# Sheet1.net
KiCad netlist of a schematic drawn in Altium Designer
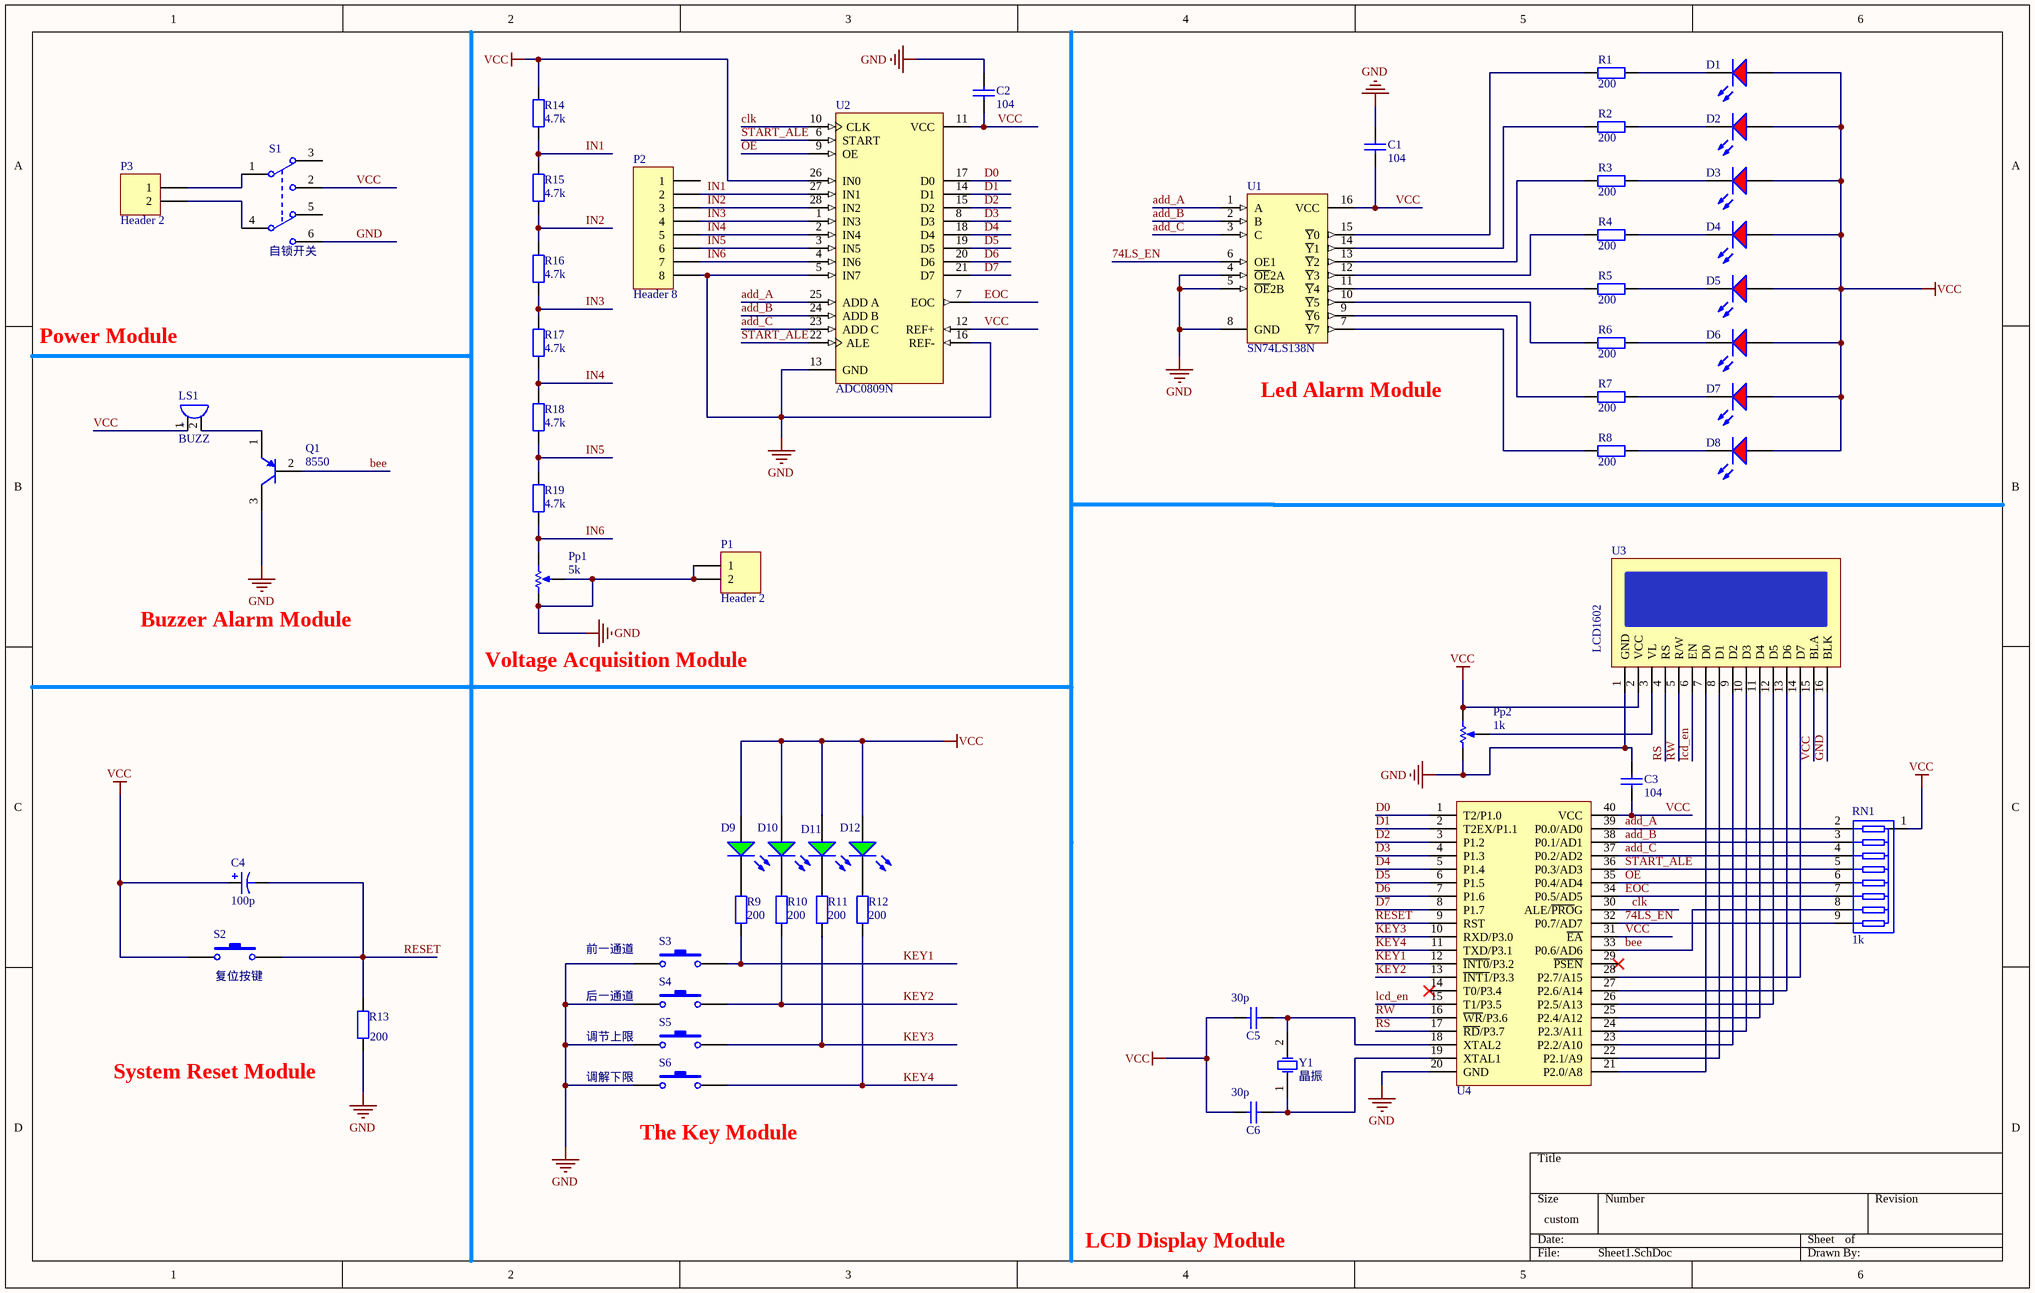
[diagram p0: Sheet1.SchDoc]

(export (version "E")
  (design (tool "Eeschema 10.0.6"))
  (components
    (comp (ref "C1")
      (value "104")
      (footprint "CAP-0.1")
      (description "Capacitor 瓷片电容 无极性电容")
      (fields (field (name "PUBLISHER") "Altium Limited"))
      (libsource (lib "02-Miscellaneous_Devices_ZSF_Library") (part "Cap_ceramic"))
    )
    (comp (ref "C2")
      (value "104")
      (footprint "CAP-0.1")
      (description "Capacitor 瓷片电容 无极性电容")
      (fields (field (name "PUBLISHER") "Altium Limited"))
      (libsource (lib "02-Miscellaneous_Devices_ZSF_Library") (part "Cap_ceramic"))
    )
    (comp (ref "C3")
      (value "104")
      (footprint "CAP-0.1")
      (description "Capacitor 瓷片电容 无极性电容")
      (fields (field (name "PUBLISHER") "Altium Limited"))
      (libsource (lib "02-Miscellaneous_Devices_ZSF_Library") (part "Cap_ceramic"))
    )
    (comp (ref "C4")
      (value "100p")
      (footprint "CAP 2.0*5*11")
      (description "Polarized Capacitor (Axial)")
      (fields (field (name "PUBLISHER") "Altium Limited"))
      (libsource (lib "02-Miscellaneous_Devices_ZSF_Library") (part "Cap Pol2"))
    )
    (comp (ref "C5")
      (value "30p")
      (footprint "CAP-0.1")
      (description "Capacitor 瓷片电容 无极性电容")
      (fields (field (name "PUBLISHER") "Altium Limited"))
      (libsource (lib "02-Miscellaneous_Devices_ZSF_Library") (part "Cap_ceramic"))
    )
    (comp (ref "C6")
      (value "30p")
      (footprint "CAP-0.1")
      (description "Capacitor 瓷片电容 无极性电容")
      (fields (field (name "PUBLISHER") "Altium Limited"))
      (libsource (lib "02-Miscellaneous_Devices_ZSF_Library") (part "Cap_ceramic"))
    )
    (comp (ref "D1")
      (value "直径5mm的红灯")
      (footprint "LED 5MM-R")
      (description "直径5mm的发光二极管")
      (libsource (lib "02-Miscellaneous_Devices_ZSF_Library") (part "LED_5#红灯"))
    )
    (comp (ref "D2")
      (value "直径5mm的红灯")
      (footprint "LED 5MM-R")
      (description "直径5mm的发光二极管")
      (libsource (lib "02-Miscellaneous_Devices_ZSF_Library") (part "LED_5#红灯"))
    )
    (comp (ref "D3")
      (value "直径5mm的红灯")
      (footprint "LED 5MM-R")
      (description "直径5mm的发光二极管")
      (libsource (lib "02-Miscellaneous_Devices_ZSF_Library") (part "LED_5#红灯"))
    )
    (comp (ref "D4")
      (value "直径5mm的红灯")
      (footprint "LED 5MM-R")
      (description "直径5mm的发光二极管")
      (libsource (lib "02-Miscellaneous_Devices_ZSF_Library") (part "LED_5#红灯"))
    )
    (comp (ref "D5")
      (value "直径5mm的红灯")
      (footprint "LED 5MM-R")
      (description "直径5mm的发光二极管")
      (libsource (lib "02-Miscellaneous_Devices_ZSF_Library") (part "LED_5#红灯"))
    )
    (comp (ref "D6")
      (value "直径5mm的红灯")
      (footprint "LED 5MM-R")
      (description "直径5mm的发光二极管")
      (libsource (lib "02-Miscellaneous_Devices_ZSF_Library") (part "LED_5#红灯"))
    )
    (comp (ref "D7")
      (value "直径5mm的红灯")
      (footprint "LED 5MM-R")
      (description "直径5mm的发光二极管")
      (libsource (lib "02-Miscellaneous_Devices_ZSF_Library") (part "LED_5#红灯"))
    )
    (comp (ref "D8")
      (value "直径5mm的红灯")
      (footprint "LED 5MM-R")
      (description "直径5mm的发光二极管")
      (libsource (lib "02-Miscellaneous_Devices_ZSF_Library") (part "LED_5#红灯"))
    )
    (comp (ref "D9")
      (value "直径5mm的绿灯")
      (footprint "LED 3MM-G")
      (description "直径5mm的发光二极管")
      (libsource (lib "02-Miscellaneous_Devices_ZSF_Library") (part "LED_5#绿灯"))
    )
    (comp (ref "D10")
      (value "直径5mm的绿灯")
      (footprint "LED 3MM-G")
      (description "直径5mm的发光二极管")
      (libsource (lib "02-Miscellaneous_Devices_ZSF_Library") (part "LED_5#绿灯"))
    )
    (comp (ref "D11")
      (value "直径5mm的绿灯")
      (footprint "LED 3MM-G")
      (description "直径5mm的发光二极管")
      (libsource (lib "02-Miscellaneous_Devices_ZSF_Library") (part "LED_5#绿灯"))
    )
    (comp (ref "D12")
      (value "直径5mm的绿灯")
      (footprint "LED 3MM-G")
      (description "直径5mm的发光二极管")
      (libsource (lib "02-Miscellaneous_Devices_ZSF_Library") (part "LED_5#绿灯"))
    )
    (comp (ref "LS1")
      (value "BUZZ")
      (footprint "Beep_small")
      (description "蜂鸣器")
      (libsource (lib "02-Miscellaneous_Devices_ZSF_Library") (part "BUZZ"))
    )
    (comp (ref "P1")
      (value "Header 2")
      (footprint "HDR1X2")
      (description "Header, 2-Pin")
      (fields (field (name "PUBLISHER") "Altium Limited"))
      (libsource (lib "03-EButterflyIntegratedLibrary") (part "Header 2"))
    )
    (comp (ref "P2")
      (value "Header 8")
      (footprint "HDR1X8")
      (description "Header, 8-Pin")
      (fields (field (name "PUBLISHER") "Altium Limited"))
      (libsource (lib "03-EButterflyIntegratedLibrary") (part "Header 8"))
    )
    (comp (ref "P3")
      (value "Header 2")
      (footprint "HX2.54-2")
      (description "Header, 2-Pin")
      (fields (field (name "PUBLISHER") "Altium Limited"))
      (libsource (lib "Miscellaneous Connectors") (part "Header 2"))
    )
    (comp (ref "Pp1")
      (value "5k")
      (footprint "RP_3296")
      (description "3296电位器")
      (libsource (lib "02-Miscellaneous_Devices_ZSF_Library") (part "RP_3296"))
    )
    (comp (ref "Pp2")
      (value "1k")
      (footprint "RP_3296")
      (description "3296电位器")
      (libsource (lib "02-Miscellaneous_Devices_ZSF_Library") (part "RP_3296"))
    )
    (comp (ref "Q1")
      (value "8550")
      (footprint "TO-92(TO-92-3)")
      (description "PNP型小功率三极管")
      (libsource (lib "02-Miscellaneous_Devices_ZSF_Library") (part "8550_TO-92"))
    )
    (comp (ref "R1")
      (value "200")
      (footprint "AXIAL-0.3-R")
      (description "Resistor 直插电阻 0.5W")
      (fields (field (name "PUBLISHER") "Altium Limited"))
      (libsource (lib "") (part "Res2_1/2W_1"))
    )
    (comp (ref "R2")
      (value "200")
      (footprint "AXIAL-0.3-R")
      (description "Resistor 直插电阻 0.5W")
      (fields (field (name "PUBLISHER") "Altium Limited"))
      (libsource (lib "") (part "Res2_1/2W_1"))
    )
    (comp (ref "R3")
      (value "200")
      (footprint "AXIAL-0.3-R")
      (description "Resistor 直插电阻 0.5W")
      (fields (field (name "PUBLISHER") "Altium Limited"))
      (libsource (lib "") (part "Res2_1/2W_1"))
    )
    (comp (ref "R4")
      (value "200")
      (footprint "AXIAL-0.3-R")
      (description "Resistor 直插电阻 0.5W")
      (fields (field (name "PUBLISHER") "Altium Limited"))
      (libsource (lib "") (part "Res2_1/2W_1"))
    )
    (comp (ref "R5")
      (value "200")
      (footprint "AXIAL-0.3-R")
      (description "Resistor 直插电阻 0.5W")
      (fields (field (name "PUBLISHER") "Altium Limited"))
      (libsource (lib "") (part "Res2_1/2W_1"))
    )
    (comp (ref "R6")
      (value "200")
      (footprint "AXIAL-0.3-R")
      (description "Resistor 直插电阻 0.5W")
      (fields (field (name "PUBLISHER") "Altium Limited"))
      (libsource (lib "") (part "Res2_1/2W_1"))
    )
    (comp (ref "R7")
      (value "200")
      (footprint "AXIAL-0.3-R")
      (description "Resistor 直插电阻 0.5W")
      (fields (field (name "PUBLISHER") "Altium Limited"))
      (libsource (lib "") (part "Res2_1/2W_1"))
    )
    (comp (ref "R8")
      (value "200")
      (footprint "AXIAL-0.3-R")
      (description "Resistor 直插电阻 0.5W")
      (fields (field (name "PUBLISHER") "Altium Limited"))
      (libsource (lib "") (part "Res2_1/2W_1"))
    )
    (comp (ref "R9")
      (value "200")
      (footprint "AXIAL-0.3-R")
      (description "Resistor 直插电阻 0.5W")
      (fields (field (name "PUBLISHER") "Altium Limited"))
      (libsource (lib "02-Miscellaneous_Devices_ZSF_Library") (part "Res2_1/2W"))
    )
    (comp (ref "R10")
      (value "200")
      (footprint "AXIAL-0.3-R")
      (description "Resistor 直插电阻 0.5W")
      (fields (field (name "PUBLISHER") "Altium Limited"))
      (libsource (lib "02-Miscellaneous_Devices_ZSF_Library") (part "Res2_1/2W"))
    )
    (comp (ref "R11")
      (value "200")
      (footprint "AXIAL-0.3-R")
      (description "Resistor 直插电阻 0.5W")
      (fields (field (name "PUBLISHER") "Altium Limited"))
      (libsource (lib "02-Miscellaneous_Devices_ZSF_Library") (part "Res2_1/2W"))
    )
    (comp (ref "R12")
      (value "200")
      (footprint "AXIAL-0.3-R")
      (description "Resistor 直插电阻 0.5W")
      (fields (field (name "PUBLISHER") "Altium Limited"))
      (libsource (lib "02-Miscellaneous_Devices_ZSF_Library") (part "Res2_1/2W"))
    )
    (comp (ref "R13")
      (value "200")
      (footprint "AXIAL-0.3-R")
      (description "Resistor 直插电阻 0.5W")
      (fields (field (name "PUBLISHER") "Altium Limited"))
      (libsource (lib "02-Miscellaneous_Devices_ZSF_Library") (part "Res2_1/2W"))
    )
    (comp (ref "R14")
      (value "4.7k")
      (footprint "AXIAL-0.3-R")
      (description "Resistor 直插电阻 0.5W")
      (fields (field (name "PUBLISHER") "Altium Limited"))
      (libsource (lib "02-Miscellaneous_Devices_ZSF_Library") (part "Res2_1/2W"))
    )
    (comp (ref "R15")
      (value "4.7k")
      (footprint "AXIAL-0.3-R")
      (description "Resistor 直插电阻 0.5W")
      (fields (field (name "PUBLISHER") "Altium Limited"))
      (libsource (lib "02-Miscellaneous_Devices_ZSF_Library") (part "Res2_1/2W"))
    )
    (comp (ref "R16")
      (value "4.7k")
      (footprint "AXIAL-0.3-R")
      (description "Resistor 直插电阻 0.5W")
      (fields (field (name "PUBLISHER") "Altium Limited"))
      (libsource (lib "02-Miscellaneous_Devices_ZSF_Library") (part "Res2_1/2W"))
    )
    (comp (ref "R17")
      (value "4.7k")
      (footprint "AXIAL-0.3-R")
      (description "Resistor 直插电阻 0.5W")
      (fields (field (name "PUBLISHER") "Altium Limited"))
      (libsource (lib "02-Miscellaneous_Devices_ZSF_Library") (part "Res2_1/2W"))
    )
    (comp (ref "R18")
      (value "4.7k")
      (footprint "AXIAL-0.3-R")
      (description "Resistor 直插电阻 0.5W")
      (fields (field (name "PUBLISHER") "Altium Limited"))
      (libsource (lib "02-Miscellaneous_Devices_ZSF_Library") (part "Res2_1/2W"))
    )
    (comp (ref "R19")
      (value "4.7k")
      (footprint "AXIAL-0.3-R")
      (description "Resistor 直插电阻 0.5W")
      (fields (field (name "PUBLISHER") "Altium Limited"))
      (libsource (lib "02-Miscellaneous_Devices_ZSF_Library") (part "Res2_1/2W"))
    )
    (comp (ref "RN1")
      (value "1k")
      (footprint "RES-PACK-DIP9")
      (description "排阻")
      (fields (field (name "Comment") "Res_Pack_Single"))
      (libsource (lib "02-Miscellaneous_Devices_ZSF_Library") (part "Res_Pack_Single"))
    )
    (comp (ref "S1")
      (value "自锁开关")
      (footprint "sw_8.5mm")
      (libsource (lib "02-Miscellaneous_Devices_ZSF_Library") (part "SW DPDT"))
    )
    (comp (ref "S2")
      (value "复位按键")
      (footprint "BUTTON_6*6")
      (description "Tactile Switch触觉开关")
      (fields (field (name "PUBLISHER") "Altium Limited"))
      (libsource (lib "02-Miscellaneous_Devices_ZSF_Library") (part "SW-PB"))
    )
    (comp (ref "S3")
      (value "前一通道")
      (footprint "BUTTON_6*6")
      (description "Tactile Switch触觉开关")
      (fields (field (name "PUBLISHER") "Altium Limited"))
      (libsource (lib "02-Miscellaneous_Devices_ZSF_Library") (part "SW-PB"))
    )
    (comp (ref "S4")
      (value "后一通道")
      (footprint "BUTTON_6*6")
      (description "Tactile Switch触觉开关")
      (fields (field (name "PUBLISHER") "Altium Limited"))
      (libsource (lib "02-Miscellaneous_Devices_ZSF_Library") (part "SW-PB"))
    )
    (comp (ref "S5")
      (value "调节上限")
      (footprint "BUTTON_6*6")
      (description "Tactile Switch触觉开关")
      (fields (field (name "PUBLISHER") "Altium Limited"))
      (libsource (lib "02-Miscellaneous_Devices_ZSF_Library") (part "SW-PB"))
    )
    (comp (ref "S6")
      (value "调解下限")
      (footprint "BUTTON_6*6")
      (description "Tactile Switch触觉开关")
      (fields (field (name "PUBLISHER") "Altium Limited"))
      (libsource (lib "02-Miscellaneous_Devices_ZSF_Library") (part "SW-PB"))
    )
    (comp (ref "U1")
      (value "SN74LS138N")
      (footprint "DIP16-300_MH")
      (description "3-Line to 8-Line Decoder / Demultiplexer")
      (fields (field (name "PUBLISHER") "Altium Limited"))
      (libsource (lib "TI Logic Decoder Demux") (part "SN74LS138N"))
    )
    (comp (ref "U2")
      (value "ADC0809N")
      (footprint "DIP28-600")
      (description "CMOS Analog-to-Digital Converter with 8-Channel Multiplexer")
      (fields (field (name "PUBLISHER") "Altium Limited"))
      (libsource (lib "TI Converter Analog to Digital") (part "ADC0809N"))
    )
    (comp (ref "U3")
      (value "LCD1602")
      (footprint "LCD1602")
      (libsource (lib "02-Miscellaneous_Devices_ZSF_Library") (part "LCD1602"))
    )
    (comp (ref "U4")
      (value "AT89C52")
      (footprint "Miscellaneous Devices ZSF:DIP-40")
      (description "AT89C52RC_DIP40")
      (libsource (lib "02-Miscellaneous_Devices_ZSF_Library") (part "AT89C52RC-DIP"))
    )
    (comp (ref "Y1")
      (value "晶振")
      (footprint "cry卧式")
      (description "直插晶振11.05292/12/16/24/MHz")
      (libsource (lib "02-Miscellaneous_Devices_ZSF_Library") (part "Crystal 11.05292/12/16/24/MHz"))
    )
  )
  (nets
    (net (code "1") (name "/74LS_EN") (class "Default")
      (node (ref "RN1") (pin "9") (pinfunction "9_9") (pintype "passive"))
      (node (ref "U1") (pin "6") (pinfunction "OE1_6") (pintype "input"))
      (node (ref "U4") (pin "32") (pinfunction "P0.7/AD7_32") (pintype "passive"))
    )
    (net (code "2") (name "/D0") (class "Default")
      (node (ref "U2") (pin "17") (pinfunction "D0_17") (pintype "tri_state"))
      (node (ref "U4") (pin "1") (pinfunction "T2/P1.0_1") (pintype "passive"))
    )
    (net (code "3") (name "/D1") (class "Default")
      (node (ref "U2") (pin "14") (pinfunction "D1_14") (pintype "tri_state"))
      (node (ref "U4") (pin "2") (pinfunction "T2EX/P1.1_2") (pintype "passive"))
    )
    (net (code "4") (name "/D2") (class "Default")
      (node (ref "U2") (pin "15") (pinfunction "D2_15") (pintype "tri_state"))
      (node (ref "U4") (pin "3") (pinfunction "P1.2_3") (pintype "passive"))
    )
    (net (code "5") (name "/D3") (class "Default")
      (node (ref "U2") (pin "8") (pinfunction "D3_8") (pintype "tri_state"))
      (node (ref "U4") (pin "4") (pinfunction "P1.3_4") (pintype "passive"))
    )
    (net (code "6") (name "/D4") (class "Default")
      (node (ref "U2") (pin "18") (pinfunction "D4_18") (pintype "tri_state"))
      (node (ref "U4") (pin "5") (pinfunction "P1.4_5") (pintype "passive"))
    )
    (net (code "7") (name "/D5") (class "Default")
      (node (ref "U2") (pin "19") (pinfunction "D5_19") (pintype "tri_state"))
      (node (ref "U4") (pin "6") (pinfunction "P1.5_6") (pintype "passive"))
    )
    (net (code "8") (name "/D6") (class "Default")
      (node (ref "U2") (pin "20") (pinfunction "D6_20") (pintype "tri_state"))
      (node (ref "U4") (pin "7") (pinfunction "P1.6_7") (pintype "passive"))
    )
    (net (code "9") (name "/D7") (class "Default")
      (node (ref "U2") (pin "21") (pinfunction "D7_21") (pintype "tri_state"))
      (node (ref "U4") (pin "8") (pinfunction "P1.7_8") (pintype "passive"))
    )
    (net (code "10") (name "/EOC") (class "Default")
      (node (ref "RN1") (pin "7") (pinfunction "7_7") (pintype "passive"))
      (node (ref "U2") (pin "7") (pinfunction "EOC_7") (pintype "output"))
      (node (ref "U4") (pin "34") (pinfunction "P0.5/AD5_34") (pintype "passive"))
    )
    (net (code "11") (name "/IN1") (class "Default")
      (node (ref "P2") (pin "2") (pinfunction "2_2") (pintype "passive"))
      (node (ref "R14") (pin "1") (pinfunction "1_1") (pintype "passive"))
      (node (ref "R15") (pin "2") (pinfunction "2_2") (pintype "passive"))
      (node (ref "U2") (pin "27") (pinfunction "IN1_27") (pintype "input"))
    )
    (net (code "12") (name "/IN2") (class "Default")
      (node (ref "P2") (pin "3") (pinfunction "3_3") (pintype "passive"))
      (node (ref "R15") (pin "1") (pinfunction "1_1") (pintype "passive"))
      (node (ref "R16") (pin "2") (pinfunction "2_2") (pintype "passive"))
      (node (ref "U2") (pin "28") (pinfunction "IN2_28") (pintype "input"))
    )
    (net (code "13") (name "/IN3") (class "Default")
      (node (ref "P2") (pin "4") (pinfunction "4_4") (pintype "passive"))
      (node (ref "R16") (pin "1") (pinfunction "1_1") (pintype "passive"))
      (node (ref "R17") (pin "2") (pinfunction "2_2") (pintype "passive"))
      (node (ref "U2") (pin "1") (pinfunction "IN3_1") (pintype "input"))
    )
    (net (code "14") (name "/IN4") (class "Default")
      (node (ref "P2") (pin "5") (pinfunction "5_5") (pintype "passive"))
      (node (ref "R17") (pin "1") (pinfunction "1_1") (pintype "passive"))
      (node (ref "R18") (pin "2") (pinfunction "2_2") (pintype "passive"))
      (node (ref "U2") (pin "2") (pinfunction "IN4_2") (pintype "input"))
    )
    (net (code "15") (name "/IN5") (class "Default")
      (node (ref "P2") (pin "6") (pinfunction "6_6") (pintype "passive"))
      (node (ref "R18") (pin "1") (pinfunction "1_1") (pintype "passive"))
      (node (ref "R19") (pin "2") (pinfunction "2_2") (pintype "passive"))
      (node (ref "U2") (pin "3") (pinfunction "IN5_3") (pintype "input"))
    )
    (net (code "16") (name "/IN6") (class "Default")
      (node (ref "P2") (pin "7") (pinfunction "7_7") (pintype "passive"))
      (node (ref "Pp1") (pin "3") (pinfunction "BOT_3") (pintype "passive"))
      (node (ref "R19") (pin "1") (pinfunction "1_1") (pintype "passive"))
      (node (ref "U2") (pin "4") (pinfunction "IN6_4") (pintype "input"))
    )
    (net (code "17") (name "/KEY1") (class "Default")
      (node (ref "R9") (pin "1") (pinfunction "1_1") (pintype "passive"))
      (node (ref "S3") (pin "2") (pinfunction "2_2") (pintype "passive"))
      (node (ref "U4") (pin "12") (pinfunction "~{INT0}/P3.2_12") (pintype "passive"))
    )
    (net (code "18") (name "/KEY2") (class "Default")
      (node (ref "R10") (pin "1") (pinfunction "1_1") (pintype "passive"))
      (node (ref "S4") (pin "2") (pinfunction "2_2") (pintype "passive"))
      (node (ref "U4") (pin "13") (pinfunction "~{INT1}/P3.3_13") (pintype "passive"))
    )
    (net (code "19") (name "/KEY3") (class "Default")
      (node (ref "R11") (pin "1") (pinfunction "1_1") (pintype "passive"))
      (node (ref "S5") (pin "2") (pinfunction "2_2") (pintype "passive"))
      (node (ref "U4") (pin "10") (pinfunction "RXD/P3.0_10") (pintype "passive"))
    )
    (net (code "20") (name "/KEY4") (class "Default")
      (node (ref "R12") (pin "1") (pinfunction "1_1") (pintype "passive"))
      (node (ref "S6") (pin "2") (pinfunction "2_2") (pintype "passive"))
      (node (ref "U4") (pin "11") (pinfunction "TXD/P3.1_11") (pintype "passive"))
    )
    (net (code "21") (name "/OE") (class "Default")
      (node (ref "RN1") (pin "6") (pinfunction "6_6") (pintype "passive"))
      (node (ref "U2") (pin "9") (pinfunction "OE_9") (pintype "input"))
      (node (ref "U4") (pin "35") (pinfunction "P0.4/AD4_35") (pintype "passive"))
    )
    (net (code "22") (name "/RESET") (class "Default")
      (node (ref "C4") (pin "2") (pinfunction "2_2") (pintype "passive"))
      (node (ref "R13") (pin "2") (pinfunction "2_2") (pintype "passive"))
      (node (ref "S2") (pin "2") (pinfunction "2_2") (pintype "passive"))
      (node (ref "U4") (pin "9") (pinfunction "RST_9") (pintype "passive"))
    )
    (net (code "23") (name "/RS") (class "Default")
      (node (ref "U3") (pin "4") (pinfunction "RS_4") (pintype "passive"))
      (node (ref "U4") (pin "17") (pinfunction "~{RD}/P3.7_17") (pintype "passive"))
    )
    (net (code "24") (name "/RW") (class "Default")
      (node (ref "U3") (pin "5") (pinfunction "R/W_5") (pintype "passive"))
      (node (ref "U4") (pin "16") (pinfunction "~{WR}/P3.6_16") (pintype "passive"))
    )
    (net (code "25") (name "/START_ALE") (class "Default")
      (node (ref "RN1") (pin "5") (pinfunction "5_5") (pintype "passive"))
      (node (ref "U2") (pin "22") (pinfunction "ALE_22") (pintype "input"))
      (node (ref "U2") (pin "6") (pinfunction "START_6") (pintype "input"))
      (node (ref "U4") (pin "36") (pinfunction "P0.3/AD3_36") (pintype "passive"))
    )
    (net (code "26") (name "/add_A") (class "Default")
      (node (ref "RN1") (pin "2") (pinfunction "2_2") (pintype "passive"))
      (node (ref "U1") (pin "1") (pinfunction "A_1") (pintype "input"))
      (node (ref "U2") (pin "25") (pinfunction "ADD_A_25") (pintype "input"))
      (node (ref "U4") (pin "39") (pinfunction "P0.0/AD0_39") (pintype "passive"))
    )
    (net (code "27") (name "/add_B") (class "Default")
      (node (ref "RN1") (pin "3") (pinfunction "3_3") (pintype "passive"))
      (node (ref "U1") (pin "2") (pinfunction "B_2") (pintype "input"))
      (node (ref "U2") (pin "24") (pinfunction "ADD_B_24") (pintype "input"))
      (node (ref "U4") (pin "38") (pinfunction "P0.1/AD1_38") (pintype "passive"))
    )
    (net (code "28") (name "/add_C") (class "Default")
      (node (ref "RN1") (pin "4") (pinfunction "4_4") (pintype "passive"))
      (node (ref "U1") (pin "3") (pinfunction "C_3") (pintype "input"))
      (node (ref "U2") (pin "23") (pinfunction "ADD_C_23") (pintype "input"))
      (node (ref "U4") (pin "37") (pinfunction "P0.2/AD2_37") (pintype "passive"))
    )
    (net (code "29") (name "/bee") (class "Default")
      (node (ref "Q1") (pin "2") (pinfunction "B_2") (pintype "passive"))
      (node (ref "RN1") (pin "8") (pinfunction "8_8") (pintype "passive"))
      (node (ref "U4") (pin "33") (pinfunction "P0.6/AD6_33") (pintype "passive"))
    )
    (net (code "30") (name "/clk") (class "Default")
      (node (ref "U2") (pin "10") (pinfunction "CLK_10") (pintype "input"))
      (node (ref "U4") (pin "30") (pinfunction "ALE/~{PRO}G_30") (pintype "passive"))
    )
    (net (code "31") (name "/lcd_en") (class "Default")
      (node (ref "U3") (pin "6") (pinfunction "EN_6") (pintype "passive"))
      (node (ref "U4") (pin "15") (pinfunction "T1/P3.5_15") (pintype "passive"))
    )
    (net (code "32") (name "GND") (class "Default")
      (node (ref "C1") (pin "2") (pinfunction "2_2") (pintype "passive"))
      (node (ref "C2") (pin "2") (pinfunction "2_2") (pintype "passive"))
      (node (ref "C3") (pin "2") (pinfunction "2_2") (pintype "passive"))
      (node (ref "P1") (pin "1") (pinfunction "1_1") (pintype "passive"))
      (node (ref "P1") (pin "2") (pinfunction "2_2") (pintype "passive"))
      (node (ref "P2") (pin "8") (pinfunction "8_8") (pintype "passive"))
      (node (ref "Pp1") (pin "1") (pinfunction "TOP_1") (pintype "passive"))
      (node (ref "Pp1") (pin "2") (pinfunction "TAP_2") (pintype "passive"))
      (node (ref "Pp2") (pin "1") (pinfunction "TOP_1") (pintype "passive"))
      (node (ref "Q1") (pin "3") (pinfunction "C_3") (pintype "passive"))
      (node (ref "R13") (pin "1") (pinfunction "1_1") (pintype "passive"))
      (node (ref "S1") (pin "6") (pinfunction "6_6") (pintype "passive"))
      (node (ref "S3") (pin "1") (pinfunction "1_1") (pintype "passive"))
      (node (ref "S4") (pin "1") (pinfunction "1_1") (pintype "passive"))
      (node (ref "S5") (pin "1") (pinfunction "1_1") (pintype "passive"))
      (node (ref "S6") (pin "1") (pinfunction "1_1") (pintype "passive"))
      (node (ref "U1") (pin "4") (pinfunction "~{OE}2A_4") (pintype "input"))
      (node (ref "U1") (pin "5") (pinfunction "~{OE}2B_5") (pintype "input"))
      (node (ref "U1") (pin "8") (pinfunction "GND_8") (pintype "power_in"))
      (node (ref "U2") (pin "13") (pinfunction "GND_13") (pintype "power_in"))
      (node (ref "U2") (pin "16") (pinfunction "REF-_16") (pintype "input"))
      (node (ref "U2") (pin "5") (pinfunction "IN7_5") (pintype "input"))
      (node (ref "U3") (pin "1") (pinfunction "GND_1") (pintype "passive"))
      (node (ref "U3") (pin "16") (pinfunction "BLK_16") (pintype "passive"))
      (node (ref "U4") (pin "20") (pinfunction "GND_20") (pintype "passive"))
    )
    (net (code "33") (name "Net-(D1-K)") (class "Default")
      (node (ref "D1") (pin "2") (pinfunction "K_2") (pintype "passive"))
      (node (ref "R1") (pin "1") (pinfunction "1_1") (pintype "passive"))
    )
    (net (code "34") (name "Net-(D2-K)") (class "Default")
      (node (ref "D2") (pin "2") (pinfunction "K_2") (pintype "passive"))
      (node (ref "R2") (pin "1") (pinfunction "1_1") (pintype "passive"))
    )
    (net (code "35") (name "Net-(D3-K)") (class "Default")
      (node (ref "D3") (pin "2") (pinfunction "K_2") (pintype "passive"))
      (node (ref "R3") (pin "1") (pinfunction "1_1") (pintype "passive"))
    )
    (net (code "36") (name "Net-(D4-K)") (class "Default")
      (node (ref "D4") (pin "2") (pinfunction "K_2") (pintype "passive"))
      (node (ref "R4") (pin "1") (pinfunction "1_1") (pintype "passive"))
    )
    (net (code "37") (name "Net-(D5-K)") (class "Default")
      (node (ref "D5") (pin "2") (pinfunction "K_2") (pintype "passive"))
      (node (ref "R5") (pin "1") (pinfunction "1_1") (pintype "passive"))
    )
    (net (code "38") (name "Net-(D6-K)") (class "Default")
      (node (ref "D6") (pin "2") (pinfunction "K_2") (pintype "passive"))
      (node (ref "R6") (pin "1") (pinfunction "1_1") (pintype "passive"))
    )
    (net (code "39") (name "Net-(D7-K)") (class "Default")
      (node (ref "D7") (pin "2") (pinfunction "K_2") (pintype "passive"))
      (node (ref "R7") (pin "1") (pinfunction "1_1") (pintype "passive"))
    )
    (net (code "40") (name "Net-(D8-K)") (class "Default")
      (node (ref "D8") (pin "2") (pinfunction "K_2") (pintype "passive"))
      (node (ref "R8") (pin "1") (pinfunction "1_1") (pintype "passive"))
    )
    (net (code "41") (name "Net-(D9-K)") (class "Default")
      (node (ref "D9") (pin "2") (pinfunction "K_2") (pintype "passive"))
      (node (ref "R9") (pin "2") (pinfunction "2_2") (pintype "passive"))
    )
    (net (code "42") (name "Net-(D10-K)") (class "Default")
      (node (ref "D10") (pin "2") (pinfunction "K_2") (pintype "passive"))
      (node (ref "R10") (pin "2") (pinfunction "2_2") (pintype "passive"))
    )
    (net (code "43") (name "Net-(D11-K)") (class "Default")
      (node (ref "D11") (pin "2") (pinfunction "K_2") (pintype "passive"))
      (node (ref "R11") (pin "2") (pinfunction "2_2") (pintype "passive"))
    )
    (net (code "44") (name "Net-(D12-K)") (class "Default")
      (node (ref "D12") (pin "2") (pinfunction "K_2") (pintype "passive"))
      (node (ref "R12") (pin "2") (pinfunction "2_2") (pintype "passive"))
    )
    (net (code "45") (name "Net-(P3-Pad1)") (class "Default")
      (node (ref "P3") (pin "1") (pinfunction "1_1") (pintype "passive"))
      (node (ref "S1") (pin "1") (pinfunction "1_1") (pintype "passive"))
    )
    (net (code "46") (name "Net-(P3-Pad2)") (class "Default")
      (node (ref "P3") (pin "2") (pinfunction "2_2") (pintype "passive"))
      (node (ref "S1") (pin "4") (pinfunction "4_4") (pintype "passive"))
    )
    (net (code "47") (name "Net-(Pp2-TAP)") (class "Default")
      (node (ref "Pp2") (pin "2") (pinfunction "TAP_2") (pintype "passive"))
      (node (ref "U3") (pin "3") (pinfunction "VL_3") (pintype "passive"))
    )
    (net (code "48") (name "Net-(Q1-E)") (class "Default")
      (node (ref "LS1") (pin "2") (pinfunction "2_2") (pintype "passive"))
      (node (ref "Q1") (pin "1") (pinfunction "E_1") (pintype "passive"))
    )
    (net (code "49") (name "Net-(U1-~{Y}0)") (class "Default")
      (node (ref "R1") (pin "2") (pinfunction "2_2") (pintype "passive"))
      (node (ref "U1") (pin "15") (pinfunction "~{Y}0_15") (pintype "output"))
    )
    (net (code "50") (name "Net-(U1-~{Y}1)") (class "Default")
      (node (ref "R2") (pin "2") (pinfunction "2_2") (pintype "passive"))
      (node (ref "U1") (pin "14") (pinfunction "~{Y}1_14") (pintype "output"))
    )
    (net (code "51") (name "Net-(U1-~{Y}2)") (class "Default")
      (node (ref "R3") (pin "2") (pinfunction "2_2") (pintype "passive"))
      (node (ref "U1") (pin "13") (pinfunction "~{Y}2_13") (pintype "output"))
    )
    (net (code "52") (name "Net-(U1-~{Y}3)") (class "Default")
      (node (ref "R4") (pin "2") (pinfunction "2_2") (pintype "passive"))
      (node (ref "U1") (pin "12") (pinfunction "~{Y}3_12") (pintype "output"))
    )
    (net (code "53") (name "Net-(U1-~{Y}4)") (class "Default")
      (node (ref "R5") (pin "2") (pinfunction "2_2") (pintype "passive"))
      (node (ref "U1") (pin "11") (pinfunction "~{Y}4_11") (pintype "output"))
    )
    (net (code "54") (name "Net-(U1-~{Y}5)") (class "Default")
      (node (ref "R6") (pin "2") (pinfunction "2_2") (pintype "passive"))
      (node (ref "U1") (pin "10") (pinfunction "~{Y}5_10") (pintype "output"))
    )
    (net (code "55") (name "Net-(U1-~{Y}6)") (class "Default")
      (node (ref "R7") (pin "2") (pinfunction "2_2") (pintype "passive"))
      (node (ref "U1") (pin "9") (pinfunction "~{Y}6_9") (pintype "output"))
    )
    (net (code "56") (name "Net-(U1-~{Y}7)") (class "Default")
      (node (ref "R8") (pin "2") (pinfunction "2_2") (pintype "passive"))
      (node (ref "U1") (pin "7") (pinfunction "~{Y}7_7") (pintype "output"))
    )
    (net (code "57") (name "Net-(U3-D0)") (class "Default")
      (node (ref "U3") (pin "7") (pinfunction "D0_7") (pintype "passive"))
      (node (ref "U4") (pin "21") (pinfunction "P2.0/A8_21") (pintype "passive"))
    )
    (net (code "58") (name "Net-(U3-D1)") (class "Default")
      (node (ref "U3") (pin "8") (pinfunction "D1_8") (pintype "passive"))
      (node (ref "U4") (pin "22") (pinfunction "P2.1/A9_22") (pintype "passive"))
    )
    (net (code "59") (name "Net-(U3-D2)") (class "Default")
      (node (ref "U3") (pin "9") (pinfunction "D2_9") (pintype "passive"))
      (node (ref "U4") (pin "23") (pinfunction "P2.2/A10_23") (pintype "passive"))
    )
    (net (code "60") (name "Net-(U3-D3)") (class "Default")
      (node (ref "U3") (pin "10") (pinfunction "D3_10") (pintype "passive"))
      (node (ref "U4") (pin "24") (pinfunction "P2.3/A11_24") (pintype "passive"))
    )
    (net (code "61") (name "Net-(U3-D4)") (class "Default")
      (node (ref "U3") (pin "11") (pinfunction "D4_11") (pintype "passive"))
      (node (ref "U4") (pin "25") (pinfunction "P2.4/A12_25") (pintype "passive"))
    )
    (net (code "62") (name "Net-(U3-D5)") (class "Default")
      (node (ref "U3") (pin "12") (pinfunction "D5_12") (pintype "passive"))
      (node (ref "U4") (pin "26") (pinfunction "P2.5/A13_26") (pintype "passive"))
    )
    (net (code "63") (name "Net-(U3-D6)") (class "Default")
      (node (ref "U3") (pin "13") (pinfunction "D6_13") (pintype "passive"))
      (node (ref "U4") (pin "27") (pinfunction "P2.6/A14_27") (pintype "passive"))
    )
    (net (code "64") (name "Net-(U3-D7)") (class "Default")
      (node (ref "U3") (pin "14") (pinfunction "D7_14") (pintype "passive"))
      (node (ref "U4") (pin "28") (pinfunction "P2.7/A15_28") (pintype "passive"))
    )
    (net (code "65") (name "Net-(U4-XTAL1)") (class "Default")
      (node (ref "C6") (pin "2") (pinfunction "2_2") (pintype "passive"))
      (node (ref "U4") (pin "19") (pinfunction "XTAL1_19") (pintype "passive"))
      (node (ref "Y1") (pin "1") (pinfunction "OSC1_1") (pintype "passive"))
    )
    (net (code "66") (name "Net-(U4-XTAL2)") (class "Default")
      (node (ref "C5") (pin "2") (pinfunction "2_2") (pintype "passive"))
      (node (ref "U4") (pin "18") (pinfunction "XTAL2_18") (pintype "passive"))
      (node (ref "Y1") (pin "2") (pinfunction "OSC2_2") (pintype "passive"))
    )
    (net (code "67") (name "VCC") (class "Default")
      (node (ref "C1") (pin "1") (pinfunction "1_1") (pintype "passive"))
      (node (ref "C2") (pin "1") (pinfunction "1_1") (pintype "passive"))
      (node (ref "C3") (pin "1") (pinfunction "1_1") (pintype "passive"))
      (node (ref "C4") (pin "1") (pinfunction "1_1") (pintype "passive"))
      (node (ref "C5") (pin "1") (pinfunction "1_1") (pintype "passive"))
      (node (ref "C6") (pin "1") (pinfunction "1_1") (pintype "passive"))
      (node (ref "D1") (pin "1") (pinfunction "A_1") (pintype "passive"))
      (node (ref "D10") (pin "1") (pinfunction "A_1") (pintype "passive"))
      (node (ref "D11") (pin "1") (pinfunction "A_1") (pintype "passive"))
      (node (ref "D12") (pin "1") (pinfunction "A_1") (pintype "passive"))
      (node (ref "D2") (pin "1") (pinfunction "A_1") (pintype "passive"))
      (node (ref "D3") (pin "1") (pinfunction "A_1") (pintype "passive"))
      (node (ref "D4") (pin "1") (pinfunction "A_1") (pintype "passive"))
      (node (ref "D5") (pin "1") (pinfunction "A_1") (pintype "passive"))
      (node (ref "D6") (pin "1") (pinfunction "A_1") (pintype "passive"))
      (node (ref "D7") (pin "1") (pinfunction "A_1") (pintype "passive"))
      (node (ref "D8") (pin "1") (pinfunction "A_1") (pintype "passive"))
      (node (ref "D9") (pin "1") (pinfunction "A_1") (pintype "passive"))
      (node (ref "LS1") (pin "1") (pinfunction "1_1") (pintype "passive"))
      (node (ref "Pp2") (pin "3") (pinfunction "BOT_3") (pintype "passive"))
      (node (ref "R14") (pin "2") (pinfunction "2_2") (pintype "passive"))
      (node (ref "RN1") (pin "1") (pinfunction "1_1") (pintype "passive"))
      (node (ref "S1") (pin "2") (pinfunction "2_2") (pintype "passive"))
      (node (ref "S2") (pin "1") (pinfunction "1_1") (pintype "passive"))
      (node (ref "U1") (pin "16") (pinfunction "VCC_16") (pintype "power_in"))
      (node (ref "U2") (pin "11") (pinfunction "VCC_11") (pintype "power_in"))
      (node (ref "U2") (pin "12") (pinfunction "REF+_12") (pintype "input"))
      (node (ref "U2") (pin "26") (pinfunction "IN0_26") (pintype "input"))
      (node (ref "U3") (pin "15") (pinfunction "BLA_15") (pintype "passive"))
      (node (ref "U3") (pin "2") (pinfunction "VCC_2") (pintype "passive"))
      (node (ref "U4") (pin "31") (pinfunction "~{EA}_31") (pintype "passive"))
      (node (ref "U4") (pin "40") (pinfunction "VCC_40") (pintype "passive"))
    )
    (net (code "68") (name "unconnected-(P2-Pad1)") (class "Default")
      (node (ref "P2") (pin "1") (pinfunction "1_1") (pintype "passive"))
    )
    (net (code "69") (name "unconnected-(S1-Pad3)") (class "Default")
      (node (ref "S1") (pin "3") (pinfunction "3_3") (pintype "passive"))
    )
    (net (code "70") (name "unconnected-(S1-Pad5)") (class "Default")
      (node (ref "S1") (pin "5") (pinfunction "5_5") (pintype "passive"))
    )
    (net (code "71") (name "unconnected-(U4-T0{slash}P3.4-Pad14)") (class "Default")
      (node (ref "U4") (pin "14") (pinfunction "T0/P3.4_14") (pintype "passive+no_connect"))
    )
    (net (code "72") (name "unconnected-(U4-~{PSEN}-Pad29)") (class "Default")
      (node (ref "U4") (pin "29") (pinfunction "~{PSEN}_29") (pintype "passive+no_connect"))
    )
  )
)
